# RS232_IrDA.net
KiCad netlist of a schematic drawn in Altium Designer
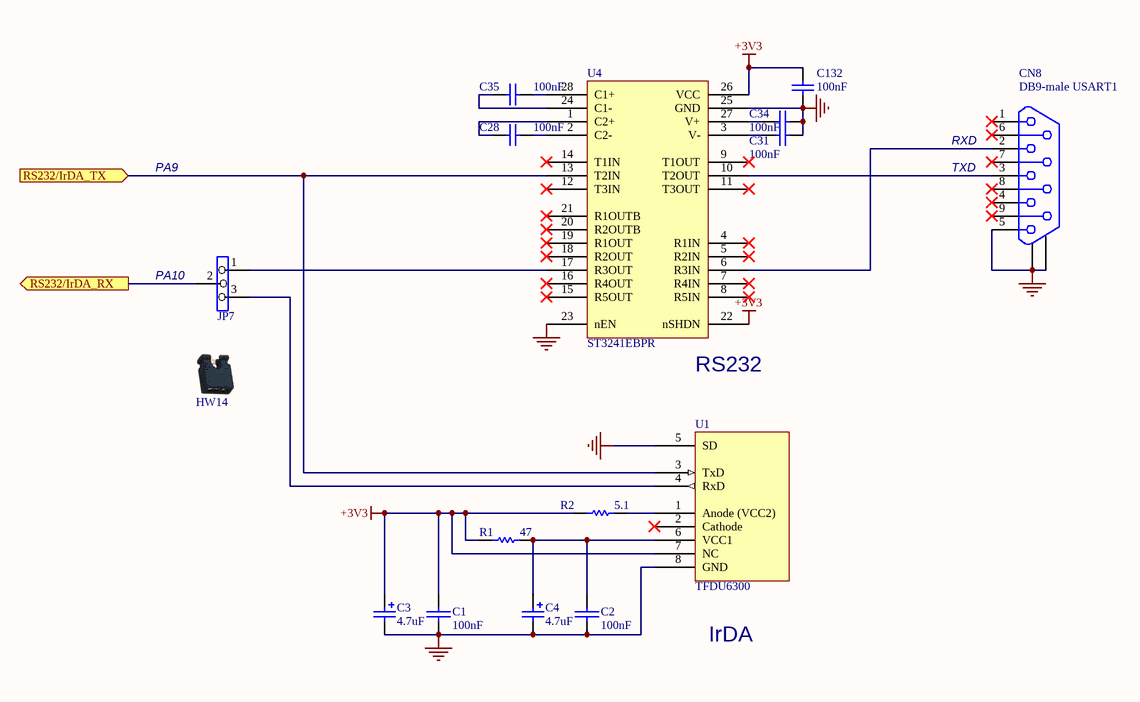
[diagram p0: RS232&IrDA.SchDoc]

(export (version "E")
  (design (tool "Eeschema 10.0.6"))
  (components
    (comp (ref "C1")
      (value "100nF")
      (footprint "0603C")
      (description "Capacitor")
      (libsource (lib "*") (part "CAP"))
    )
    (comp (ref "C2")
      (value "100nF")
      (footprint "0603C")
      (description "Capacitor")
      (libsource (lib "*") (part "CAP"))
    )
    (comp (ref "C3")
      (value "4.7uF")
      (footprint "TAN-A")
      (description "Polarized Capacitor (Radial)")
      (fields (field (name "PUBLISHER") "Altium Limited"))
      (libsource (lib "Miscellaneous Devices") (part "Cap Pol1"))
    )
    (comp (ref "C4")
      (value "4.7uF")
      (footprint "TAN-A")
      (description "Polarized Capacitor (Radial)")
      (fields (field (name "PUBLISHER") "Altium Limited"))
      (libsource (lib "Miscellaneous Devices") (part "Cap Pol1"))
    )
    (comp (ref "C28")
      (value "100nF")
      (footprint "0603C")
      (description "Capacitor")
      (fields (field (name "PUBLISHER") "Altium Limited"))
      (libsource (lib "Miscellaneous Devices") (part "Cap"))
    )
    (comp (ref "C31")
      (value "100nF")
      (footprint "0603C")
      (description "Capacitor")
      (fields (field (name "PUBLISHER") "Altium Limited"))
      (libsource (lib "Miscellaneous Devices") (part "Cap"))
    )
    (comp (ref "C34")
      (value "100nF")
      (footprint "0603C")
      (description "Capacitor")
      (fields (field (name "PUBLISHER") "Altium Limited"))
      (libsource (lib "Miscellaneous Devices") (part "Cap"))
    )
    (comp (ref "C35")
      (value "100nF")
      (footprint "0603C")
      (description "Capacitor")
      (fields (field (name "PUBLISHER") "Altium Limited"))
      (libsource (lib "Miscellaneous Devices") (part "Cap"))
    )
    (comp (ref "C132")
      (value "100nF")
      (footprint "0603C")
      (description "Capacitor")
      (fields (field (name "PUBLISHER") "Altium Limited"))
      (libsource (lib "Miscellaneous Devices") (part "Cap"))
    )
    (comp (ref "CN8")
      (value "DB9-male USART1")
      (footprint "DB9/M")
      (libsource (lib "mb1045") (part "DB9-USART"))
    )
    (comp (ref "HW14") (value "JUMPER_OPEN") (libsource (lib "mb1045") (part "JUMPER_OPEN")))
    (comp (ref "JP7") (value "~") (footprint "SIP3") (libsource (lib "STR910_SCHLIB") (part "Jumper3")))
    (comp (ref "R1")
      (value "47")
      (footprint "0603R")
      (description "Resistor")
      (fields (field (name "PUBLISHER") "Altium Limited"))
      (libsource (lib "Miscellaneous Devices") (part "Res1"))
    )
    (comp (ref "R2")
      (value "5.1")
      (footprint "0603R")
      (description "Resistor")
      (fields (field (name "PUBLISHER") "Altium Limited"))
      (libsource (lib "Miscellaneous Devices") (part "Res1"))
    )
    (comp (ref "U1")
      (value "TFDU6300")
      (footprint "IR_VISHAY3")
      (description "TFDU4300")
      (libsource (lib "*") (part "TFDU4300"))
    )
    (comp (ref "U4")
      (value "ST3241EBPR")
      (footprint "SSOP28_0R65_10R2X7R8")
      (libsource (lib "*") (part "ST3241"))
    )
  )
  (nets
    (net (code "1") (name "+3V3") (class "Default")
      (node (ref "C1") (pin "1") (pinfunction "1_1") (pintype "passive"))
      (node (ref "C132") (pin "1") (pinfunction "1_1") (pintype "passive"))
      (node (ref "C3") (pin "1") (pinfunction "1_1") (pintype "passive"))
      (node (ref "R1") (pin "1") (pinfunction "1_1") (pintype "passive"))
      (node (ref "R2") (pin "1") (pinfunction "1_1") (pintype "passive"))
      (node (ref "U1") (pin "7") (pinfunction "NC_7") (pintype "passive"))
      (node (ref "U4") (pin "22") (pinfunction "nSHDN_22") (pintype "passive"))
      (node (ref "U4") (pin "26") (pinfunction "VCC_26") (pintype "passive"))
    )
    (net (code "2") (name "/RS232{slash}IrDA_RX") (class "Default")
      (node (ref "JP7") (pin "2") (pintype "passive"))
    )
    (net (code "3") (name "/RS232{slash}IrDA_TX") (class "Default")
      (node (ref "U1") (pin "3") (pinfunction "TxD_3") (pintype "input"))
      (node (ref "U4") (pin "13") (pinfunction "T2IN_13") (pintype "passive"))
    )
    (net (code "4") (name "GND") (class "Default")
      (node (ref "C1") (pin "2") (pinfunction "2_2") (pintype "passive"))
      (node (ref "C132") (pin "2") (pinfunction "2_2") (pintype "passive"))
      (node (ref "C2") (pin "2") (pinfunction "2_2") (pintype "passive"))
      (node (ref "C3") (pin "2") (pinfunction "2_2") (pintype "passive"))
      (node (ref "C31") (pin "1") (pinfunction "1_1") (pintype "passive"))
      (node (ref "C34") (pin "1") (pinfunction "1_1") (pintype "passive"))
      (node (ref "C4") (pin "2") (pinfunction "2_2") (pintype "passive"))
      (node (ref "CN8") (pin "10") (pinfunction "10_10") (pintype "passive"))
      (node (ref "CN8") (pin "11") (pinfunction "11_11") (pintype "passive"))
      (node (ref "CN8") (pin "5") (pinfunction "5_5") (pintype "passive"))
      (node (ref "U1") (pin "5") (pinfunction "SD_5") (pintype "passive"))
      (node (ref "U1") (pin "8") (pinfunction "GND_8") (pintype "passive"))
      (node (ref "U4") (pin "23") (pinfunction "nEN_23") (pintype "passive"))
      (node (ref "U4") (pin "25") (pinfunction "GND_25") (pintype "passive"))
    )
    (net (code "5") (name "Net-(U1-Anode_(VCC2))") (class "Default")
      (node (ref "R2") (pin "2") (pinfunction "2_2") (pintype "passive"))
      (node (ref "U1") (pin "1") (pinfunction "Anode_(VCC2)_1") (pintype "passive"))
    )
    (net (code "6") (name "Net-(U1-RxD)") (class "Default")
      (node (ref "JP7") (pin "3") (pintype "passive"))
      (node (ref "U1") (pin "4") (pinfunction "RxD_4") (pintype "output"))
    )
    (net (code "7") (name "Net-(U1-VCC1)") (class "Default")
      (node (ref "C2") (pin "1") (pinfunction "1_1") (pintype "passive"))
      (node (ref "C4") (pin "1") (pinfunction "1_1") (pintype "passive"))
      (node (ref "R1") (pin "2") (pinfunction "2_2") (pintype "passive"))
      (node (ref "U1") (pin "6") (pinfunction "VCC1_6") (pintype "passive"))
    )
    (net (code "8") (name "Net-(U4-C1+)") (class "Default")
      (node (ref "C35") (pin "2") (pinfunction "2_2") (pintype "passive"))
      (node (ref "U4") (pin "28") (pinfunction "C1+_28") (pintype "passive"))
    )
    (net (code "9") (name "Net-(U4-C1-)") (class "Default")
      (node (ref "C35") (pin "1") (pinfunction "1_1") (pintype "passive"))
      (node (ref "U4") (pin "24") (pinfunction "C1-_24") (pintype "passive"))
    )
    (net (code "10") (name "Net-(U4-C2+)") (class "Default")
      (node (ref "C28") (pin "1") (pinfunction "1_1") (pintype "passive"))
      (node (ref "U4") (pin "1") (pinfunction "C2+_1") (pintype "passive"))
    )
    (net (code "11") (name "Net-(U4-C2-)") (class "Default")
      (node (ref "C28") (pin "2") (pinfunction "2_2") (pintype "passive"))
      (node (ref "U4") (pin "2") (pinfunction "C2-_2") (pintype "passive"))
    )
    (net (code "12") (name "Net-(U4-R3IN)") (class "Default")
      (node (ref "CN8") (pin "2") (pinfunction "2_2") (pintype "passive"))
      (node (ref "U4") (pin "6") (pinfunction "R3IN_6") (pintype "passive"))
    )
    (net (code "13") (name "Net-(U4-R3OUT)") (class "Default")
      (node (ref "JP7") (pin "1") (pintype "passive"))
      (node (ref "U4") (pin "17") (pinfunction "R3OUT_17") (pintype "passive"))
    )
    (net (code "14") (name "Net-(U4-T2OUT)") (class "Default")
      (node (ref "CN8") (pin "3") (pinfunction "3_3") (pintype "passive"))
      (node (ref "U4") (pin "10") (pinfunction "T2OUT_10") (pintype "passive"))
    )
    (net (code "15") (name "Net-(U4-V+)") (class "Default")
      (node (ref "C34") (pin "2") (pinfunction "2_2") (pintype "passive"))
      (node (ref "U4") (pin "27") (pinfunction "V+_27") (pintype "passive"))
    )
    (net (code "16") (name "Net-(U4-V-)") (class "Default")
      (node (ref "C31") (pin "2") (pinfunction "2_2") (pintype "passive"))
      (node (ref "U4") (pin "3") (pinfunction "V-_3") (pintype "passive"))
    )
    (net (code "17") (name "unconnected-(CN8-Pad1)") (class "Default")
      (node (ref "CN8") (pin "1") (pinfunction "1_1") (pintype "passive+no_connect"))
    )
    (net (code "18") (name "unconnected-(CN8-Pad4)") (class "Default")
      (node (ref "CN8") (pin "4") (pinfunction "4_4") (pintype "passive+no_connect"))
    )
    (net (code "19") (name "unconnected-(CN8-Pad6)") (class "Default")
      (node (ref "CN8") (pin "6") (pinfunction "6_6") (pintype "passive+no_connect"))
    )
    (net (code "20") (name "unconnected-(CN8-Pad7)") (class "Default")
      (node (ref "CN8") (pin "7") (pinfunction "7_7") (pintype "passive+no_connect"))
    )
    (net (code "21") (name "unconnected-(CN8-Pad8)") (class "Default")
      (node (ref "CN8") (pin "8") (pinfunction "8_8") (pintype "passive+no_connect"))
    )
    (net (code "22") (name "unconnected-(CN8-Pad9)") (class "Default")
      (node (ref "CN8") (pin "9") (pinfunction "9_9") (pintype "passive+no_connect"))
    )
    (net (code "23") (name "unconnected-(U1-Cathode-Pad2)") (class "Default")
      (node (ref "U1") (pin "2") (pinfunction "Cathode_2") (pintype "passive+no_connect"))
    )
    (net (code "24") (name "unconnected-(U4-R1IN-Pad4)") (class "Default")
      (node (ref "U4") (pin "4") (pinfunction "R1IN_4") (pintype "passive+no_connect"))
    )
    (net (code "25") (name "unconnected-(U4-R1OUT-Pad19)") (class "Default")
      (node (ref "U4") (pin "19") (pinfunction "R1OUT_19") (pintype "passive+no_connect"))
    )
    (net (code "26") (name "unconnected-(U4-R1OUTB-Pad21)") (class "Default")
      (node (ref "U4") (pin "21") (pinfunction "R1OUTB_21") (pintype "passive+no_connect"))
    )
    (net (code "27") (name "unconnected-(U4-R2IN-Pad5)") (class "Default")
      (node (ref "U4") (pin "5") (pinfunction "R2IN_5") (pintype "passive+no_connect"))
    )
    (net (code "28") (name "unconnected-(U4-R2OUT-Pad18)") (class "Default")
      (node (ref "U4") (pin "18") (pinfunction "R2OUT_18") (pintype "passive+no_connect"))
    )
    (net (code "29") (name "unconnected-(U4-R2OUTB-Pad20)") (class "Default")
      (node (ref "U4") (pin "20") (pinfunction "R2OUTB_20") (pintype "passive+no_connect"))
    )
    (net (code "30") (name "unconnected-(U4-R4IN-Pad7)") (class "Default")
      (node (ref "U4") (pin "7") (pinfunction "R4IN_7") (pintype "passive+no_connect"))
    )
    (net (code "31") (name "unconnected-(U4-R4OUT-Pad16)") (class "Default")
      (node (ref "U4") (pin "16") (pinfunction "R4OUT_16") (pintype "passive+no_connect"))
    )
    (net (code "32") (name "unconnected-(U4-R5IN-Pad8)") (class "Default")
      (node (ref "U4") (pin "8") (pinfunction "R5IN_8") (pintype "passive+no_connect"))
    )
    (net (code "33") (name "unconnected-(U4-R5OUT-Pad15)") (class "Default")
      (node (ref "U4") (pin "15") (pinfunction "R5OUT_15") (pintype "passive+no_connect"))
    )
    (net (code "34") (name "unconnected-(U4-T1IN-Pad14)") (class "Default")
      (node (ref "U4") (pin "14") (pinfunction "T1IN_14") (pintype "passive+no_connect"))
    )
    (net (code "35") (name "unconnected-(U4-T1OUT-Pad9)") (class "Default")
      (node (ref "U4") (pin "9") (pinfunction "T1OUT_9") (pintype "passive+no_connect"))
    )
    (net (code "36") (name "unconnected-(U4-T3IN-Pad12)") (class "Default")
      (node (ref "U4") (pin "12") (pinfunction "T3IN_12") (pintype "passive+no_connect"))
    )
    (net (code "37") (name "unconnected-(U4-T3OUT-Pad11)") (class "Default")
      (node (ref "U4") (pin "11") (pinfunction "T3OUT_11") (pintype "passive+no_connect"))
    )
  )
)
